# Output_1Wire.net
KiCad netlist of a schematic drawn in Altium Designer
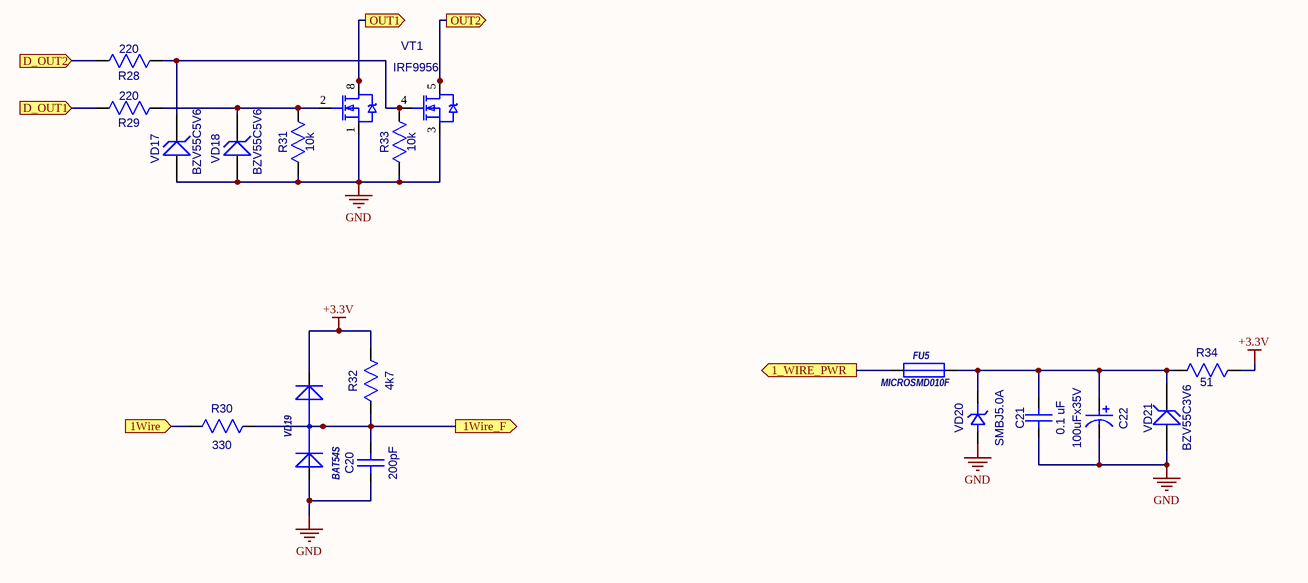
[diagram p0: Output&1Wire.SchDoc]

(export (version "E")
  (design (tool "Eeschema 10.0.6"))
  (components
    (comp (ref "C20")
      (value "200pF")
      (footprint "CC0603-3M")
      (description "CC0603")
      (libsource (lib "gprs_modem") (part "CC0603"))
    )
    (comp (ref "C21")
      (value "0.1 uF")
      (footprint "CC0603-3M")
      (description "CC0603")
      (libsource (lib "*") (part "CC0603"))
    )
    (comp (ref "C22")
      (value "100uFx35V")
      (footprint "CC20X2.54")
      (description "CAP0.25")
      (libsource (lib "gprs_modem") (part "CAP0.25"))
    )
    (comp (ref "FU5")
      (value "MICROSMD010F")
      (footprint "RC1210")
      (description "MICROSMD")
      (libsource (lib "*") (part "MICROSMD"))
    )
    (comp (ref "R28")
      (value "220")
      (footprint "RC0603-3M")
      (description "RC0603")
      (libsource (lib "*") (part "RC0603"))
    )
    (comp (ref "R29")
      (value "220")
      (footprint "RC0603-3M")
      (description "RC0603")
      (libsource (lib "*") (part "RC0603"))
    )
    (comp (ref "R30")
      (value "330")
      (footprint "RC0603-3M")
      (description "RC0603")
      (libsource (lib "gprs_modem") (part "RC0603"))
    )
    (comp (ref "R31")
      (value "10k")
      (footprint "RC0603-3M")
      (description "RC0603")
      (libsource (lib "*") (part "RC0603"))
    )
    (comp (ref "R32")
      (value "4k7")
      (footprint "RC0603-3M")
      (description "RC0603")
      (libsource (lib "gprs_modem") (part "RC0603"))
    )
    (comp (ref "R33")
      (value "10k")
      (footprint "RC0603-3M")
      (description "RC0603")
      (libsource (lib "*") (part "RC0603"))
    )
    (comp (ref "R34")
      (value "51")
      (footprint "RC1206-2M")
      (description "RC1206")
      (libsource (lib "*") (part "RC1206"))
    )
    (comp (ref "VD17")
      (value "BZV55C5V6")
      (footprint "SOD-80")
      (description "BZV55C3V0")
      (libsource (lib "*") (part "BZV55C3V0"))
    )
    (comp (ref "VD18")
      (value "BZV55C5V6")
      (footprint "SOD-80")
      (description "BZV55C3V0")
      (libsource (lib "*") (part "BZV55C3V0"))
    )
    (comp (ref "VD19")
      (value "BAT54S")
      (footprint "SOT-23(GSD)")
      (description "1.0 Ampere General Purpose Rectifier")
      (libsource (lib "gprs_modem") (part "BAT54S"))
    )
    (comp (ref "VD20")
      (value "SMBJ5.0A")
      (footprint "SMB")
      (description "SMBJ")
      (libsource (lib "*") (part "SMBJ"))
    )
    (comp (ref "VD21")
      (value "BZV55C3V6")
      (footprint "SOD-80")
      (description "BZV55C12")
      (libsource (lib "*") (part "BZV55C12"))
    )
    (comp (ref "VT1") (value "IRF9956") (footprint "SO-8") (libsource (lib "*") (part "IRF9956")))
  )
  (nets
    (net (code "1") (name "+3.3V") (class "Default")
      (node (ref "R32") (pin "2") (pinfunction "B_2") (pintype "passive"))
      (node (ref "R34") (pin "2") (pinfunction "B_2") (pintype "passive"))
      (node (ref "VD19") (pin "2") (pinfunction "K_2") (pintype "passive"))
    )
    (net (code "2") (name "/1Wire") (class "Default")
      (node (ref "R30") (pin "1") (pinfunction "A_1") (pintype "passive"))
    )
    (net (code "3") (name "/1Wire_F") (class "Default")
      (node (ref "C20") (pin "2") (pinfunction "B_2") (pintype "passive"))
      (node (ref "R30") (pin "2") (pinfunction "B_2") (pintype "passive"))
      (node (ref "R32") (pin "1") (pinfunction "A_1") (pintype "passive"))
      (node (ref "VD19") (pin "3") (pinfunction "AK_3") (pintype "passive"))
    )
    (net (code "4") (name "/1_WIRE_PWR") (class "Default") (node (ref "FU5") (pin "2") (pintype "passive")))
    (net (code "5") (name "/D_OUT1") (class "Default")
      (node (ref "R29") (pin "1") (pinfunction "A_1") (pintype "passive"))
    )
    (net (code "6") (name "/D_OUT2") (class "Default")
      (node (ref "R28") (pin "1") (pinfunction "A_1") (pintype "passive"))
    )
    (net (code "7") (name "/OUT1") (class "Default")
      (node (ref "VT1") (pin "7") (pinfunction "D_7") (pintype "passive"))
      (node (ref "VT1") (pin "8") (pinfunction "D_8") (pintype "passive"))
    )
    (net (code "8") (name "/OUT2") (class "Default")
      (node (ref "VT1") (pin "5") (pinfunction "D_5") (pintype "passive"))
      (node (ref "VT1") (pin "6") (pinfunction "D_6") (pintype "passive"))
    )
    (net (code "9") (name "GND") (class "Default")
      (node (ref "C20") (pin "1") (pinfunction "A_1") (pintype "passive"))
      (node (ref "C21") (pin "1") (pinfunction "A_1") (pintype "passive"))
      (node (ref "C22") (pin "2") (pinfunction "minus_2") (pintype "passive"))
      (node (ref "R31") (pin "2") (pinfunction "B_2") (pintype "passive"))
      (node (ref "R33") (pin "2") (pinfunction "B_2") (pintype "passive"))
      (node (ref "VD17") (pin "1") (pinfunction "A_1") (pintype "passive"))
      (node (ref "VD18") (pin "1") (pinfunction "A_1") (pintype "passive"))
      (node (ref "VD19") (pin "1") (pinfunction "A_1") (pintype "passive"))
      (node (ref "VD20") (pin "1") (pinfunction "A_1") (pintype "passive"))
      (node (ref "VD21") (pin "1") (pinfunction "A_1") (pintype "passive"))
      (node (ref "VT1") (pin "1") (pinfunction "S_1") (pintype "passive"))
      (node (ref "VT1") (pin "3") (pinfunction "S_3") (pintype "passive"))
    )
    (net (code "10") (name "Net-(C21-B)") (class "Default")
      (node (ref "C21") (pin "2") (pinfunction "B_2") (pintype "passive"))
      (node (ref "C22") (pin "1") (pinfunction "plus_1") (pintype "passive"))
      (node (ref "FU5") (pin "1") (pintype "passive"))
      (node (ref "R34") (pin "1") (pinfunction "A_1") (pintype "passive"))
      (node (ref "VD20") (pin "2") (pinfunction "K_2") (pintype "passive"))
      (node (ref "VD21") (pin "2") (pintype "passive"))
    )
    (net (code "11") (name "Net-(R28-B)") (class "Default")
      (node (ref "R28") (pin "2") (pinfunction "B_2") (pintype "passive"))
      (node (ref "R33") (pin "1") (pinfunction "A_1") (pintype "passive"))
      (node (ref "VD17") (pin "2") (pintype "passive"))
      (node (ref "VT1") (pin "4") (pinfunction "G_4") (pintype "passive"))
    )
    (net (code "12") (name "Net-(R29-B)") (class "Default")
      (node (ref "R29") (pin "2") (pinfunction "B_2") (pintype "passive"))
      (node (ref "R31") (pin "1") (pinfunction "A_1") (pintype "passive"))
      (node (ref "VD18") (pin "2") (pintype "passive"))
      (node (ref "VT1") (pin "2") (pinfunction "G_2") (pintype "passive"))
    )
  )
)
